# s_analyzer.net
KiCad netlist of a schematic drawn in EAGLE
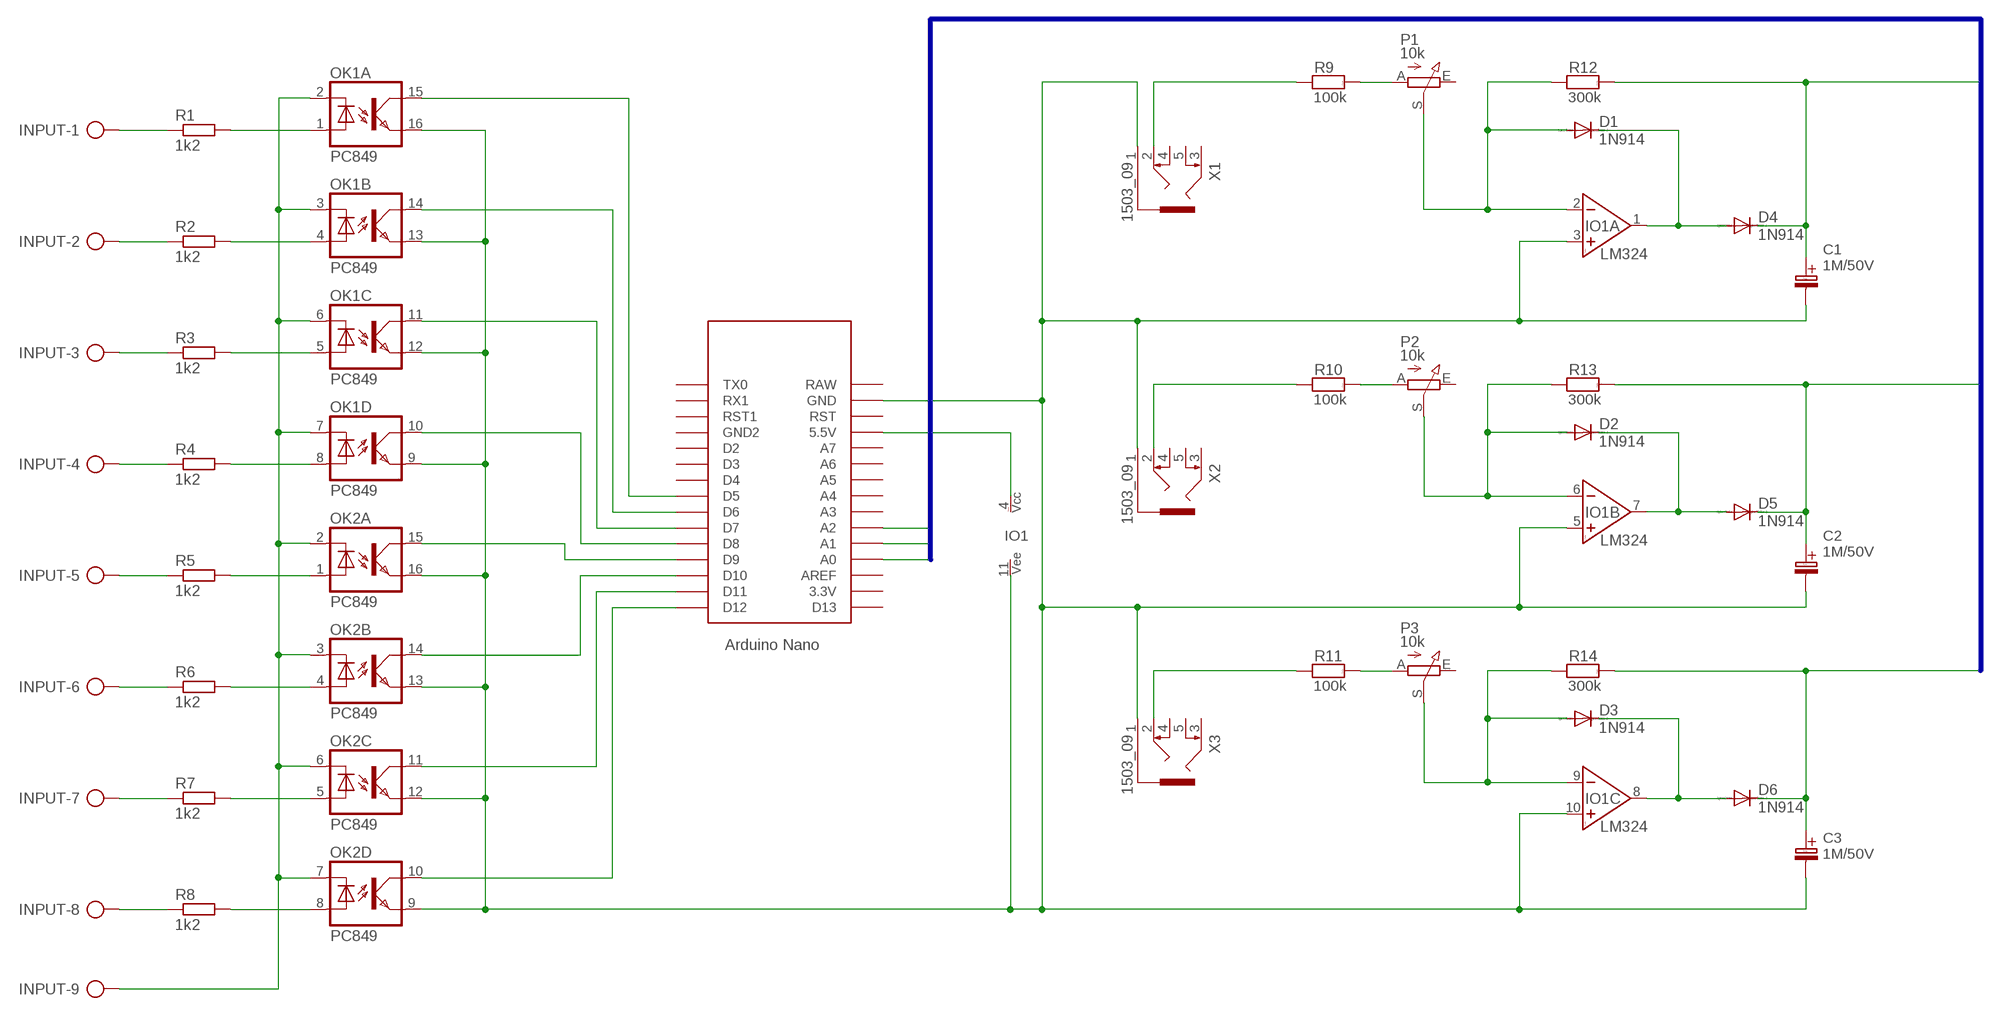
[diagram p0: schematic, sheet 1]

(export (version "E")
  (design (tool "Eeschema 10.0.6"))
  (components
    (comp (ref "C1")
      (value "1M/50V")
      (footprint "eagle-import:C_EL_2")
      (libsource (lib "eagle-import") (part "1M/50V"))
    )
    (comp (ref "C2")
      (value "1M/50V")
      (footprint "eagle-import:C_EL_2")
      (libsource (lib "eagle-import") (part "1M/50V"))
    )
    (comp (ref "C3")
      (value "1M/50V")
      (footprint "eagle-import:C_EL_2")
      (libsource (lib "eagle-import") (part "1M/50V"))
    )
    (comp (ref "D1")
      (value "1N914")
      (footprint "eagle-import:DO35-7")
      (libsource (lib "eagle-import") (part "1N4148DO35-7"))
    )
    (comp (ref "D2")
      (value "1N914")
      (footprint "eagle-import:DO35-7")
      (libsource (lib "eagle-import") (part "1N4148DO35-7"))
    )
    (comp (ref "D3")
      (value "1N914")
      (footprint "eagle-import:DO35-7")
      (libsource (lib "eagle-import") (part "1N4148DO35-7"))
    )
    (comp (ref "D4")
      (value "1N914")
      (footprint "eagle-import:DO35-7")
      (libsource (lib "eagle-import") (part "1N4148DO35-7"))
    )
    (comp (ref "D5")
      (value "1N914")
      (footprint "eagle-import:DO35-7")
      (libsource (lib "eagle-import") (part "1N4148DO35-7"))
    )
    (comp (ref "D6")
      (value "1N914")
      (footprint "eagle-import:DO35-7")
      (libsource (lib "eagle-import") (part "1N4148DO35-7"))
    )
    (comp (ref "INPUT")
      (value "AK500/9")
      (footprint "eagle-import:AK500_9")
      (libsource (lib "eagle-import") (part "AK500/9"))
    )
    (comp (ref "IO1")
      (value "LM324")
      (footprint "eagle-import:DIL14")
      (libsource (lib "eagle-import") (part "LM324"))
    )
    (comp (ref "OK1")
      (value "PC849")
      (footprint "eagle-import:DIL16")
      (libsource (lib "eagle-import") (part "PC849"))
    )
    (comp (ref "OK2")
      (value "PC849")
      (footprint "eagle-import:DIL16")
      (libsource (lib "eagle-import") (part "PC849"))
    )
    (comp (ref "P1")
      (value "10k")
      (footprint "eagle-import:PT10V")
      (libsource (lib "eagle-import") (part "TRIMRPT10V"))
    )
    (comp (ref "P2")
      (value "10k")
      (footprint "eagle-import:PT10V")
      (libsource (lib "eagle-import") (part "TRIMRPT10V"))
    )
    (comp (ref "P3")
      (value "10k")
      (footprint "eagle-import:PT10V")
      (libsource (lib "eagle-import") (part "TRIMRPT10V"))
    )
    (comp (ref "R1")
      (value "1k2")
      (footprint "eagle-import:0204_5")
      (libsource (lib "eagle-import") (part "R-EU_0204/5"))
    )
    (comp (ref "R2")
      (value "1k2")
      (footprint "eagle-import:0204_5")
      (libsource (lib "eagle-import") (part "R-EU_0204/5"))
    )
    (comp (ref "R3")
      (value "1k2")
      (footprint "eagle-import:0204_5")
      (libsource (lib "eagle-import") (part "R-EU_0204/5"))
    )
    (comp (ref "R4")
      (value "1k2")
      (footprint "eagle-import:0204_5")
      (libsource (lib "eagle-import") (part "R-EU_0204/5"))
    )
    (comp (ref "R5")
      (value "1k2")
      (footprint "eagle-import:0204_5")
      (libsource (lib "eagle-import") (part "R-EU_0204/5"))
    )
    (comp (ref "R6")
      (value "1k2")
      (footprint "eagle-import:0204_5")
      (libsource (lib "eagle-import") (part "R-EU_0204/5"))
    )
    (comp (ref "R7")
      (value "1k2")
      (footprint "eagle-import:0204_5")
      (libsource (lib "eagle-import") (part "R-EU_0204/5"))
    )
    (comp (ref "R8")
      (value "1k2")
      (footprint "eagle-import:0204_5")
      (libsource (lib "eagle-import") (part "R-EU_0204/5"))
    )
    (comp (ref "R9")
      (value "100k")
      (footprint "eagle-import:R_7,5")
      (libsource (lib "eagle-import") (part "330K"))
    )
    (comp (ref "R10")
      (value "100k")
      (footprint "eagle-import:R_7,5")
      (libsource (lib "eagle-import") (part "330K"))
    )
    (comp (ref "R11")
      (value "100k")
      (footprint "eagle-import:R_7,5")
      (libsource (lib "eagle-import") (part "330K"))
    )
    (comp (ref "R12")
      (value "300k")
      (footprint "eagle-import:R_7,5")
      (libsource (lib "eagle-import") (part "100K"))
    )
    (comp (ref "R13")
      (value "300k")
      (footprint "eagle-import:R_7,5")
      (libsource (lib "eagle-import") (part "100K"))
    )
    (comp (ref "R14")
      (value "300k")
      (footprint "eagle-import:R_7,5")
      (libsource (lib "eagle-import") (part "100K"))
    )
    (comp (ref "U$1")
      (value "NANO")
      (footprint "eagle-import:NANO")
      (libsource (lib "eagle-import") (part "NANO"))
    )
    (comp (ref "X1")
      (value "1503_09")
      (footprint "eagle-import:1503_09")
      (libsource (lib "eagle-import") (part "1503_09"))
    )
    (comp (ref "X2")
      (value "1503_09")
      (footprint "eagle-import:1503_09")
      (libsource (lib "eagle-import") (part "1503_09"))
    )
    (comp (ref "X3")
      (value "1503_09")
      (footprint "eagle-import:1503_09")
      (libsource (lib "eagle-import") (part "1503_09"))
    )
  )
  (nets
    (net (code "1") (name "/A0") (class "Default")
      (node (ref "C1") (pin "C+") (pinfunction "C_EL+_C+") (pintype "passive"))
      (node (ref "D4") (pin "C") (pinfunction "C_C") (pintype "passive"))
      (node (ref "R12") (pin "2") (pinfunction "2_2") (pintype "passive"))
      (node (ref "U$1") (pin "A0") (pinfunction "A0_A0") (pintype "bidirectional"))
    )
    (net (code "2") (name "/A1") (class "Default")
      (node (ref "C2") (pin "C+") (pinfunction "C_EL+_C+") (pintype "passive"))
      (node (ref "D5") (pin "C") (pinfunction "C_C") (pintype "passive"))
      (node (ref "R13") (pin "2") (pinfunction "2_2") (pintype "passive"))
      (node (ref "U$1") (pin "A1") (pinfunction "A1_A1") (pintype "bidirectional"))
    )
    (net (code "3") (name "/A2") (class "Default")
      (node (ref "C3") (pin "C+") (pinfunction "C_EL+_C+") (pintype "passive"))
      (node (ref "D6") (pin "C") (pinfunction "C_C") (pintype "passive"))
      (node (ref "R14") (pin "2") (pinfunction "2_2") (pintype "passive"))
      (node (ref "U$1") (pin "A2") (pinfunction "A2_A2") (pintype "bidirectional"))
    )
    (net (code "4") (name "Net-(C1-C_EL-)") (class "Default")
      (node (ref "C1") (pin "C-") (pinfunction "C_EL-_C-") (pintype "passive"))
      (node (ref "C2") (pin "C-") (pinfunction "C_EL-_C-") (pintype "passive"))
      (node (ref "C3") (pin "C-") (pinfunction "C_EL-_C-") (pintype "passive"))
      (node (ref "IO1") (pin "10") (pinfunction "NEIN+_10") (pintype "input"))
      (node (ref "IO1") (pin "11") (pinfunction "VEE_11") (pintype "power_in"))
      (node (ref "IO1") (pin "3") (pinfunction "NEIN+_3") (pintype "input"))
      (node (ref "IO1") (pin "5") (pinfunction "NEIN+_5") (pintype "input"))
      (node (ref "OK1") (pin "12") (pinfunction "EMI_12") (pintype "passive"))
      (node (ref "OK1") (pin "13") (pinfunction "EMI_13") (pintype "passive"))
      (node (ref "OK1") (pin "16") (pinfunction "EMI_16") (pintype "passive"))
      (node (ref "OK1") (pin "9") (pinfunction "EMI_9") (pintype "passive"))
      (node (ref "OK2") (pin "12") (pinfunction "EMI_12") (pintype "passive"))
      (node (ref "OK2") (pin "13") (pinfunction "EMI_13") (pintype "passive"))
      (node (ref "OK2") (pin "16") (pinfunction "EMI_16") (pintype "passive"))
      (node (ref "OK2") (pin "9") (pinfunction "EMI_9") (pintype "passive"))
      (node (ref "U$1") (pin "GND") (pinfunction "GND_GND") (pintype "bidirectional"))
      (node (ref "X1") (pin "1") (pinfunction "1_1") (pintype "passive"))
      (node (ref "X2") (pin "1") (pinfunction "1_1") (pintype "passive"))
      (node (ref "X3") (pin "1") (pinfunction "1_1") (pintype "passive"))
    )
    (net (code "5") (name "Net-(INPUTA-KL)") (class "Default")
      (node (ref "INPUT") (pin "1") (pinfunction "KL_1") (pintype "passive"))
      (node (ref "R1") (pin "1") (pinfunction "1_1") (pintype "passive"))
    )
    (net (code "6") (name "Net-(INPUTB-KL)") (class "Default")
      (node (ref "INPUT") (pin "2") (pinfunction "KL_2") (pintype "passive"))
      (node (ref "R2") (pin "1") (pinfunction "1_1") (pintype "passive"))
    )
    (net (code "7") (name "Net-(INPUTC-KL)") (class "Default")
      (node (ref "INPUT") (pin "3") (pinfunction "KL_3") (pintype "passive"))
      (node (ref "R3") (pin "1") (pinfunction "1_1") (pintype "passive"))
    )
    (net (code "8") (name "Net-(INPUTD-KL)") (class "Default")
      (node (ref "INPUT") (pin "4") (pinfunction "KL_4") (pintype "passive"))
      (node (ref "R4") (pin "1") (pinfunction "1_1") (pintype "passive"))
    )
    (net (code "9") (name "Net-(INPUTE-KL)") (class "Default")
      (node (ref "INPUT") (pin "5") (pinfunction "KL_5") (pintype "passive"))
      (node (ref "R5") (pin "1") (pinfunction "1_1") (pintype "passive"))
    )
    (net (code "10") (name "Net-(INPUTF-KL)") (class "Default")
      (node (ref "INPUT") (pin "6") (pinfunction "KL_6") (pintype "passive"))
      (node (ref "R6") (pin "1") (pinfunction "1_1") (pintype "passive"))
    )
    (net (code "11") (name "Net-(INPUTG-KL)") (class "Default")
      (node (ref "INPUT") (pin "7") (pinfunction "KL_7") (pintype "passive"))
      (node (ref "R7") (pin "1") (pinfunction "1_1") (pintype "passive"))
    )
    (net (code "12") (name "Net-(INPUTH-KL)") (class "Default")
      (node (ref "INPUT") (pin "8") (pinfunction "KL_8") (pintype "passive"))
      (node (ref "R8") (pin "1") (pinfunction "1_1") (pintype "passive"))
    )
    (net (code "13") (name "Net-(INPUTI-KL)") (class "Default")
      (node (ref "INPUT") (pin "9") (pinfunction "KL_9") (pintype "passive"))
      (node (ref "OK1") (pin "2") (pinfunction "C_2") (pintype "passive"))
      (node (ref "OK1") (pin "3") (pinfunction "C_3") (pintype "passive"))
      (node (ref "OK1") (pin "6") (pinfunction "C_6") (pintype "passive"))
      (node (ref "OK1") (pin "7") (pinfunction "C_7") (pintype "passive"))
      (node (ref "OK2") (pin "2") (pinfunction "C_2") (pintype "passive"))
      (node (ref "OK2") (pin "3") (pinfunction "C_3") (pintype "passive"))
      (node (ref "OK2") (pin "6") (pinfunction "C_6") (pintype "passive"))
      (node (ref "OK2") (pin "7") (pinfunction "C_7") (pintype "passive"))
    )
    (net (code "14") (name "Net-(IO1A-IN-)") (class "Default")
      (node (ref "D1") (pin "A") (pinfunction "A_A") (pintype "passive"))
      (node (ref "IO1") (pin "2") (pinfunction "IN-_2") (pintype "input"))
      (node (ref "P1") (pin "S") (pinfunction "S_S") (pintype "passive"))
      (node (ref "R12") (pin "1") (pinfunction "1_1") (pintype "passive"))
    )
    (net (code "15") (name "Net-(IO1A-VYSTUP)") (class "Default")
      (node (ref "D1") (pin "C") (pinfunction "C_C") (pintype "passive"))
      (node (ref "D4") (pin "A") (pinfunction "A_A") (pintype "passive"))
      (node (ref "IO1") (pin "1") (pinfunction "VYSTUP_1") (pintype "output"))
    )
    (net (code "16") (name "Net-(IO1B-IN-)") (class "Default")
      (node (ref "D2") (pin "A") (pinfunction "A_A") (pintype "passive"))
      (node (ref "IO1") (pin "6") (pinfunction "IN-_6") (pintype "input"))
      (node (ref "P2") (pin "S") (pinfunction "S_S") (pintype "passive"))
      (node (ref "R13") (pin "1") (pinfunction "1_1") (pintype "passive"))
    )
    (net (code "17") (name "Net-(IO1B-VYSTUP)") (class "Default")
      (node (ref "D2") (pin "C") (pinfunction "C_C") (pintype "passive"))
      (node (ref "D5") (pin "A") (pinfunction "A_A") (pintype "passive"))
      (node (ref "IO1") (pin "7") (pinfunction "VYSTUP_7") (pintype "output"))
    )
    (net (code "18") (name "Net-(IO1C-IN-)") (class "Default")
      (node (ref "D3") (pin "A") (pinfunction "A_A") (pintype "passive"))
      (node (ref "IO1") (pin "9") (pinfunction "IN-_9") (pintype "input"))
      (node (ref "P3") (pin "S") (pinfunction "S_S") (pintype "passive"))
      (node (ref "R14") (pin "1") (pinfunction "1_1") (pintype "passive"))
    )
    (net (code "19") (name "Net-(IO1C-VYSTUP)") (class "Default")
      (node (ref "D3") (pin "C") (pinfunction "C_C") (pintype "passive"))
      (node (ref "D6") (pin "A") (pinfunction "A_A") (pintype "passive"))
      (node (ref "IO1") (pin "8") (pinfunction "VYSTUP_8") (pintype "output"))
    )
    (net (code "20") (name "Net-(IO1E-VCC)") (class "Default")
      (node (ref "IO1") (pin "4") (pinfunction "VCC_4") (pintype "power_in"))
      (node (ref "U$1") (pin "5V") (pinfunction "5.5V_5V") (pintype "bidirectional"))
    )
    (net (code "21") (name "Net-(OK1A-A)") (class "Default")
      (node (ref "OK1") (pin "1") (pinfunction "A_1") (pintype "passive"))
      (node (ref "R1") (pin "2") (pinfunction "2_2") (pintype "passive"))
    )
    (net (code "22") (name "Net-(OK1A-COL)") (class "Default")
      (node (ref "OK1") (pin "15") (pinfunction "COL_15") (pintype "passive"))
      (node (ref "U$1") (pin "D5") (pinfunction "D5_D5") (pintype "bidirectional"))
    )
    (net (code "23") (name "Net-(OK1B-A)") (class "Default")
      (node (ref "OK1") (pin "4") (pinfunction "A_4") (pintype "passive"))
      (node (ref "R2") (pin "2") (pinfunction "2_2") (pintype "passive"))
    )
    (net (code "24") (name "Net-(OK1B-COL)") (class "Default")
      (node (ref "OK1") (pin "14") (pinfunction "COL_14") (pintype "passive"))
      (node (ref "U$1") (pin "D6") (pinfunction "D6_D6") (pintype "bidirectional"))
    )
    (net (code "25") (name "Net-(OK1C-A)") (class "Default")
      (node (ref "OK1") (pin "5") (pinfunction "A_5") (pintype "passive"))
      (node (ref "R3") (pin "2") (pinfunction "2_2") (pintype "passive"))
    )
    (net (code "26") (name "Net-(OK1C-COL)") (class "Default")
      (node (ref "OK1") (pin "11") (pinfunction "COL_11") (pintype "passive"))
      (node (ref "U$1") (pin "D7") (pinfunction "D7_D7") (pintype "bidirectional"))
    )
    (net (code "27") (name "Net-(OK1D-A)") (class "Default")
      (node (ref "OK1") (pin "8") (pinfunction "A_8") (pintype "passive"))
      (node (ref "R4") (pin "2") (pinfunction "2_2") (pintype "passive"))
    )
    (net (code "28") (name "Net-(OK1D-COL)") (class "Default")
      (node (ref "OK1") (pin "10") (pinfunction "COL_10") (pintype "passive"))
      (node (ref "U$1") (pin "D8") (pinfunction "D8_D8") (pintype "bidirectional"))
    )
    (net (code "29") (name "Net-(OK2A-A)") (class "Default")
      (node (ref "OK2") (pin "1") (pinfunction "A_1") (pintype "passive"))
      (node (ref "R5") (pin "2") (pinfunction "2_2") (pintype "passive"))
    )
    (net (code "30") (name "Net-(OK2A-COL)") (class "Default")
      (node (ref "OK2") (pin "15") (pinfunction "COL_15") (pintype "passive"))
      (node (ref "U$1") (pin "D9") (pinfunction "D9_D9") (pintype "bidirectional"))
    )
    (net (code "31") (name "Net-(OK2B-A)") (class "Default")
      (node (ref "OK2") (pin "4") (pinfunction "A_4") (pintype "passive"))
      (node (ref "R6") (pin "2") (pinfunction "2_2") (pintype "passive"))
    )
    (net (code "32") (name "Net-(OK2B-COL)") (class "Default")
      (node (ref "OK2") (pin "14") (pinfunction "COL_14") (pintype "passive"))
      (node (ref "U$1") (pin "D10") (pinfunction "D10_D10") (pintype "bidirectional"))
    )
    (net (code "33") (name "Net-(OK2C-A)") (class "Default")
      (node (ref "OK2") (pin "5") (pinfunction "A_5") (pintype "passive"))
      (node (ref "R7") (pin "2") (pinfunction "2_2") (pintype "passive"))
    )
    (net (code "34") (name "Net-(OK2C-COL)") (class "Default")
      (node (ref "OK2") (pin "11") (pinfunction "COL_11") (pintype "passive"))
      (node (ref "U$1") (pin "D11") (pinfunction "D11_D11") (pintype "bidirectional"))
    )
    (net (code "35") (name "Net-(OK2D-A)") (class "Default")
      (node (ref "OK2") (pin "8") (pinfunction "A_8") (pintype "passive"))
      (node (ref "R8") (pin "2") (pinfunction "2_2") (pintype "passive"))
    )
    (net (code "36") (name "Net-(OK2D-COL)") (class "Default")
      (node (ref "OK2") (pin "10") (pinfunction "COL_10") (pintype "passive"))
      (node (ref "U$1") (pin "D12") (pinfunction "D12_D12") (pintype "bidirectional"))
    )
    (net (code "37") (name "Net-(P1-PadA)") (class "Default")
      (node (ref "P1") (pin "A") (pinfunction "A_A") (pintype "passive"))
      (node (ref "R9") (pin "2") (pinfunction "2_2") (pintype "passive"))
    )
    (net (code "38") (name "Net-(P2-PadA)") (class "Default")
      (node (ref "P2") (pin "A") (pinfunction "A_A") (pintype "passive"))
      (node (ref "R10") (pin "2") (pinfunction "2_2") (pintype "passive"))
    )
    (net (code "39") (name "Net-(P3-PadA)") (class "Default")
      (node (ref "P3") (pin "A") (pinfunction "A_A") (pintype "passive"))
      (node (ref "R11") (pin "2") (pinfunction "2_2") (pintype "passive"))
    )
    (net (code "40") (name "Net-(R9-Pad1)") (class "Default")
      (node (ref "R9") (pin "1") (pinfunction "1_1") (pintype "passive"))
      (node (ref "X1") (pin "2") (pinfunction "2_2") (pintype "passive"))
    )
    (net (code "41") (name "Net-(R10-Pad1)") (class "Default")
      (node (ref "R10") (pin "1") (pinfunction "1_1") (pintype "passive"))
      (node (ref "X2") (pin "2") (pinfunction "2_2") (pintype "passive"))
    )
    (net (code "42") (name "Net-(R11-Pad1)") (class "Default")
      (node (ref "R11") (pin "1") (pinfunction "1_1") (pintype "passive"))
      (node (ref "X3") (pin "2") (pinfunction "2_2") (pintype "passive"))
    )
    (net (code "43") (name "unconnected-(P1-PadE)") (class "Default")
      (node (ref "P1") (pin "E") (pinfunction "E_E") (pintype "passive"))
    )
    (net (code "44") (name "unconnected-(P2-PadE)") (class "Default")
      (node (ref "P2") (pin "E") (pinfunction "E_E") (pintype "passive"))
    )
    (net (code "45") (name "unconnected-(P3-PadE)") (class "Default")
      (node (ref "P3") (pin "E") (pinfunction "E_E") (pintype "passive"))
    )
    (net (code "46") (name "unconnected-(U$1-GND2-PadGND1)") (class "Default")
      (node (ref "U$1") (pin "GND1") (pinfunction "GND2_GND1") (pintype "bidirectional"))
    )
    (net (code "47") (name "unconnected-(U$1-Pad3.3V)") (class "Default")
      (node (ref "U$1") (pin "3.3V") (pinfunction "3.3V_3.3V") (pintype "bidirectional"))
    )
    (net (code "48") (name "unconnected-(U$1-PadA3)") (class "Default")
      (node (ref "U$1") (pin "A3") (pinfunction "A3_A3") (pintype "bidirectional"))
    )
    (net (code "49") (name "unconnected-(U$1-PadA4)") (class "Default")
      (node (ref "U$1") (pin "A4") (pinfunction "A4_A4") (pintype "bidirectional"))
    )
    (net (code "50") (name "unconnected-(U$1-PadA5)") (class "Default")
      (node (ref "U$1") (pin "A5") (pinfunction "A5_A5") (pintype "bidirectional"))
    )
    (net (code "51") (name "unconnected-(U$1-PadA6)") (class "Default")
      (node (ref "U$1") (pin "A6") (pinfunction "A6_A6") (pintype "bidirectional"))
    )
    (net (code "52") (name "unconnected-(U$1-PadA7)") (class "Default")
      (node (ref "U$1") (pin "A7") (pinfunction "A7_A7") (pintype "bidirectional"))
    )
    (net (code "53") (name "unconnected-(U$1-PadAREF)") (class "Default")
      (node (ref "U$1") (pin "AREF") (pinfunction "AREF_AREF") (pintype "bidirectional"))
    )
    (net (code "54") (name "unconnected-(U$1-PadD2)") (class "Default")
      (node (ref "U$1") (pin "D2") (pinfunction "D2_D2") (pintype "bidirectional"))
    )
    (net (code "55") (name "unconnected-(U$1-PadD3)") (class "Default")
      (node (ref "U$1") (pin "D3") (pinfunction "D3_D3") (pintype "bidirectional"))
    )
    (net (code "56") (name "unconnected-(U$1-PadD4)") (class "Default")
      (node (ref "U$1") (pin "D4") (pinfunction "D4_D4") (pintype "bidirectional"))
    )
    (net (code "57") (name "unconnected-(U$1-PadD13)") (class "Default")
      (node (ref "U$1") (pin "D13") (pinfunction "D13_D13") (pintype "bidirectional"))
    )
    (net (code "58") (name "unconnected-(U$1-PadICSP1)") (class "Default")
      (node (ref "U$1") (pin "ICSP1") (pinfunction "ICSP1_ICSP1") (pintype "bidirectional"))
    )
    (net (code "59") (name "unconnected-(U$1-PadICSP2)") (class "Default")
      (node (ref "U$1") (pin "ICSP2") (pinfunction "ICSP2_ICSP2") (pintype "bidirectional"))
    )
    (net (code "60") (name "unconnected-(U$1-PadICSP3)") (class "Default")
      (node (ref "U$1") (pin "ICSP3") (pinfunction "ICSP3_ICSP3") (pintype "bidirectional"))
    )
    (net (code "61") (name "unconnected-(U$1-PadICSP4)") (class "Default")
      (node (ref "U$1") (pin "ICSP4") (pinfunction "ICSP4_ICSP4") (pintype "bidirectional"))
    )
    (net (code "62") (name "unconnected-(U$1-PadICSP5)") (class "Default")
      (node (ref "U$1") (pin "ICSP5") (pinfunction "ICSP5_ICSP5") (pintype "bidirectional"))
    )
    (net (code "63") (name "unconnected-(U$1-PadICSP6)") (class "Default")
      (node (ref "U$1") (pin "ICSP6") (pinfunction "ICSP6_ICSP6") (pintype "bidirectional"))
    )
    (net (code "64") (name "unconnected-(U$1-PadRAW)") (class "Default")
      (node (ref "U$1") (pin "RAW") (pinfunction "RAW_RAW") (pintype "bidirectional"))
    )
    (net (code "65") (name "unconnected-(U$1-PadRST)") (class "Default")
      (node (ref "U$1") (pin "RST") (pinfunction "RST_RST") (pintype "bidirectional"))
    )
    (net (code "66") (name "unconnected-(U$1-PadRST1)") (class "Default")
      (node (ref "U$1") (pin "RST1") (pinfunction "RST1_RST1") (pintype "bidirectional"))
    )
    (net (code "67") (name "unconnected-(U$1-PadRX1)") (class "Default")
      (node (ref "U$1") (pin "RX1") (pinfunction "RX1_RX1") (pintype "bidirectional"))
    )
    (net (code "68") (name "unconnected-(U$1-PadTX0)") (class "Default")
      (node (ref "U$1") (pin "TX0") (pinfunction "TX0_TX0") (pintype "bidirectional"))
    )
    (net (code "69") (name "unconnected-(X1-Pad3)") (class "Default")
      (node (ref "X1") (pin "3") (pinfunction "3_3") (pintype "passive"))
    )
    (net (code "70") (name "unconnected-(X1-Pad4)") (class "Default")
      (node (ref "X1") (pin "4") (pinfunction "4_4") (pintype "passive"))
    )
    (net (code "71") (name "unconnected-(X1-Pad5)") (class "Default")
      (node (ref "X1") (pin "5") (pinfunction "5_5") (pintype "passive"))
    )
    (net (code "72") (name "unconnected-(X2-Pad3)") (class "Default")
      (node (ref "X2") (pin "3") (pinfunction "3_3") (pintype "passive"))
    )
    (net (code "73") (name "unconnected-(X2-Pad4)") (class "Default")
      (node (ref "X2") (pin "4") (pinfunction "4_4") (pintype "passive"))
    )
    (net (code "74") (name "unconnected-(X2-Pad5)") (class "Default")
      (node (ref "X2") (pin "5") (pinfunction "5_5") (pintype "passive"))
    )
    (net (code "75") (name "unconnected-(X3-Pad3)") (class "Default")
      (node (ref "X3") (pin "3") (pinfunction "3_3") (pintype "passive"))
    )
    (net (code "76") (name "unconnected-(X3-Pad4)") (class "Default")
      (node (ref "X3") (pin "4") (pinfunction "4_4") (pintype "passive"))
    )
    (net (code "77") (name "unconnected-(X3-Pad5)") (class "Default")
      (node (ref "X3") (pin "5") (pinfunction "5_5") (pintype "passive"))
    )
  )
)
